# atmega.net
KiCad netlist of a schematic drawn in EAGLE
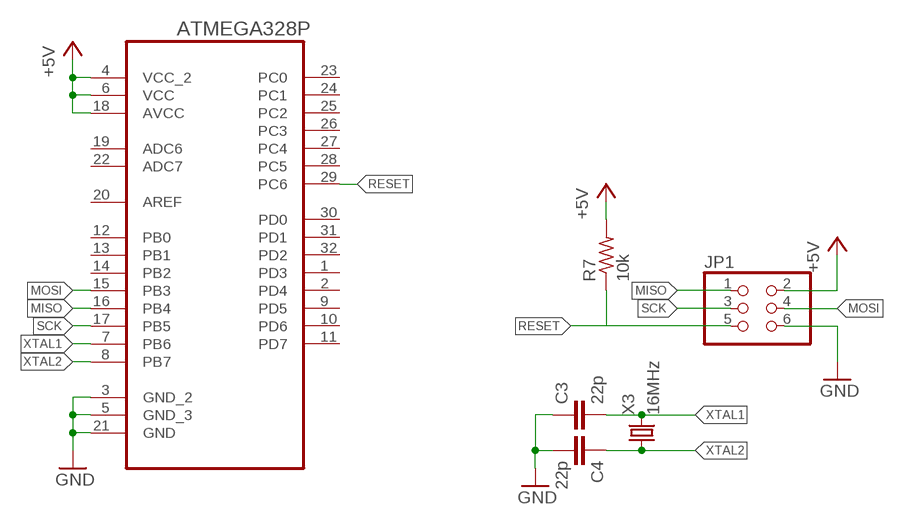
[diagram p0: schematic, sheet 1]

(export (version "E")
  (design (tool "Eeschema 10.0.6"))
  (components
    (comp (ref "ATMEGA328P")
      (value "ATMEGA328P-AU")
      (footprint "eagle-import:QFP80P900X900X120-32N")
      (libsource (lib "eagle-import") (part "ATMEGA328P-AU"))
    )
    (comp (ref "C3")
      (value "22p")
      (footprint "eagle-import:C0805K")
      (libsource (lib "eagle-import") (part "C-EUC0805K"))
    )
    (comp (ref "C4")
      (value "22p")
      (footprint "eagle-import:C0805K")
      (libsource (lib "eagle-import") (part "C-EUC0805K"))
    )
    (comp (ref "JP1")
      (value "PINHD-2X3")
      (footprint "eagle-import:2X03")
      (libsource (lib "eagle-import") (part "PINHD-2X3"))
    )
    (comp (ref "R7")
      (value "10k")
      (footprint "eagle-import:R0805")
      (libsource (lib "eagle-import") (part "R-US_R0805"))
    )
    (comp (ref "X3")
      (value "16MHz")
      (footprint "eagle-import:QS")
      (libsource (lib "eagle-import") (part "CRYSTAL"))
    )
  )
  (nets
    (net (code "1") (name "+5V") (class "Default")
      (node (ref "ATMEGA328P") (pin "18") (pinfunction "AVCC_18") (pintype "power_in"))
      (node (ref "ATMEGA328P") (pin "4") (pinfunction "VCC_2_4") (pintype "power_in"))
      (node (ref "ATMEGA328P") (pin "6") (pinfunction "VCC_6") (pintype "power_in"))
      (node (ref "JP1") (pin "2") (pinfunction "2_2") (pintype "passive"))
      (node (ref "R7") (pin "2") (pinfunction "2_2") (pintype "passive"))
    )
    (net (code "2") (name "GND") (class "Default")
      (node (ref "ATMEGA328P") (pin "21") (pinfunction "GND_21") (pintype "passive"))
      (node (ref "ATMEGA328P") (pin "3") (pinfunction "GND_2_3") (pintype "passive"))
      (node (ref "ATMEGA328P") (pin "5") (pinfunction "GND_3_5") (pintype "passive"))
      (node (ref "C3") (pin "1") (pinfunction "1_1") (pintype "passive"))
      (node (ref "C4") (pin "2") (pinfunction "2_2") (pintype "passive"))
      (node (ref "JP1") (pin "6") (pinfunction "6_6") (pintype "passive"))
    )
    (net (code "3") (name "MISO") (class "Default")
      (node (ref "ATMEGA328P") (pin "16") (pinfunction "PB4_16") (pintype "bidirectional"))
      (node (ref "JP1") (pin "1") (pinfunction "1_1") (pintype "passive"))
    )
    (net (code "4") (name "MOSI") (class "Default")
      (node (ref "ATMEGA328P") (pin "15") (pinfunction "PB3_15") (pintype "bidirectional"))
      (node (ref "JP1") (pin "4") (pinfunction "4_4") (pintype "passive"))
    )
    (net (code "5") (name "RESET") (class "Default")
      (node (ref "ATMEGA328P") (pin "29") (pinfunction "PC6_29") (pintype "bidirectional"))
      (node (ref "JP1") (pin "5") (pinfunction "5_5") (pintype "passive"))
      (node (ref "R7") (pin "1") (pinfunction "1_1") (pintype "passive"))
    )
    (net (code "6") (name "SCK") (class "Default")
      (node (ref "ATMEGA328P") (pin "17") (pinfunction "PB5_17") (pintype "bidirectional"))
      (node (ref "JP1") (pin "3") (pinfunction "3_3") (pintype "passive"))
    )
    (net (code "7") (name "XTAL1") (class "Default")
      (node (ref "ATMEGA328P") (pin "7") (pinfunction "PB6_7") (pintype "bidirectional"))
      (node (ref "C3") (pin "2") (pinfunction "2_2") (pintype "passive"))
      (node (ref "X3") (pin "2") (pinfunction "2_2") (pintype "passive"))
    )
    (net (code "8") (name "XTAL2") (class "Default")
      (node (ref "ATMEGA328P") (pin "8") (pinfunction "PB7_8") (pintype "bidirectional"))
      (node (ref "C4") (pin "1") (pinfunction "1_1") (pintype "passive"))
      (node (ref "X3") (pin "1") (pinfunction "1_1") (pintype "passive"))
    )
    (net (code "9") (name "unconnected-(ATMEGA328P-ADC6-Pad19)") (class "Default")
      (node (ref "ATMEGA328P") (pin "19") (pinfunction "ADC6_19") (pintype "input"))
    )
    (net (code "10") (name "unconnected-(ATMEGA328P-ADC7-Pad22)") (class "Default")
      (node (ref "ATMEGA328P") (pin "22") (pinfunction "ADC7_22") (pintype "input"))
    )
    (net (code "11") (name "unconnected-(ATMEGA328P-AREF-Pad20)") (class "Default")
      (node (ref "ATMEGA328P") (pin "20") (pinfunction "AREF_20") (pintype "input"))
    )
    (net (code "12") (name "unconnected-(ATMEGA328P-PB0-Pad12)") (class "Default")
      (node (ref "ATMEGA328P") (pin "12") (pinfunction "PB0_12") (pintype "bidirectional"))
    )
    (net (code "13") (name "unconnected-(ATMEGA328P-PB1-Pad13)") (class "Default")
      (node (ref "ATMEGA328P") (pin "13") (pinfunction "PB1_13") (pintype "bidirectional"))
    )
    (net (code "14") (name "unconnected-(ATMEGA328P-PB2-Pad14)") (class "Default")
      (node (ref "ATMEGA328P") (pin "14") (pinfunction "PB2_14") (pintype "bidirectional"))
    )
    (net (code "15") (name "unconnected-(ATMEGA328P-PC0-Pad23)") (class "Default")
      (node (ref "ATMEGA328P") (pin "23") (pinfunction "PC0_23") (pintype "bidirectional"))
    )
    (net (code "16") (name "unconnected-(ATMEGA328P-PC1-Pad24)") (class "Default")
      (node (ref "ATMEGA328P") (pin "24") (pinfunction "PC1_24") (pintype "bidirectional"))
    )
    (net (code "17") (name "unconnected-(ATMEGA328P-PC2-Pad25)") (class "Default")
      (node (ref "ATMEGA328P") (pin "25") (pinfunction "PC2_25") (pintype "bidirectional"))
    )
    (net (code "18") (name "unconnected-(ATMEGA328P-PC3-Pad26)") (class "Default")
      (node (ref "ATMEGA328P") (pin "26") (pinfunction "PC3_26") (pintype "bidirectional"))
    )
    (net (code "19") (name "unconnected-(ATMEGA328P-PC4-Pad27)") (class "Default")
      (node (ref "ATMEGA328P") (pin "27") (pinfunction "PC4_27") (pintype "bidirectional"))
    )
    (net (code "20") (name "unconnected-(ATMEGA328P-PC5-Pad28)") (class "Default")
      (node (ref "ATMEGA328P") (pin "28") (pinfunction "PC5_28") (pintype "bidirectional"))
    )
    (net (code "21") (name "unconnected-(ATMEGA328P-PD0-Pad30)") (class "Default")
      (node (ref "ATMEGA328P") (pin "30") (pinfunction "PD0_30") (pintype "bidirectional"))
    )
    (net (code "22") (name "unconnected-(ATMEGA328P-PD1-Pad31)") (class "Default")
      (node (ref "ATMEGA328P") (pin "31") (pinfunction "PD1_31") (pintype "bidirectional"))
    )
    (net (code "23") (name "unconnected-(ATMEGA328P-PD2-Pad32)") (class "Default")
      (node (ref "ATMEGA328P") (pin "32") (pinfunction "PD2_32") (pintype "bidirectional"))
    )
    (net (code "24") (name "unconnected-(ATMEGA328P-PD3-Pad1)") (class "Default")
      (node (ref "ATMEGA328P") (pin "1") (pinfunction "PD3_1") (pintype "bidirectional"))
    )
    (net (code "25") (name "unconnected-(ATMEGA328P-PD4-Pad2)") (class "Default")
      (node (ref "ATMEGA328P") (pin "2") (pinfunction "PD4_2") (pintype "bidirectional"))
    )
    (net (code "26") (name "unconnected-(ATMEGA328P-PD5-Pad9)") (class "Default")
      (node (ref "ATMEGA328P") (pin "9") (pinfunction "PD5_9") (pintype "bidirectional"))
    )
    (net (code "27") (name "unconnected-(ATMEGA328P-PD6-Pad10)") (class "Default")
      (node (ref "ATMEGA328P") (pin "10") (pinfunction "PD6_10") (pintype "bidirectional"))
    )
    (net (code "28") (name "unconnected-(ATMEGA328P-PD7-Pad11)") (class "Default")
      (node (ref "ATMEGA328P") (pin "11") (pinfunction "PD7_11") (pintype "bidirectional"))
    )
  )
)
